# Power.net
KiCad netlist of a schematic drawn in Altium Designer
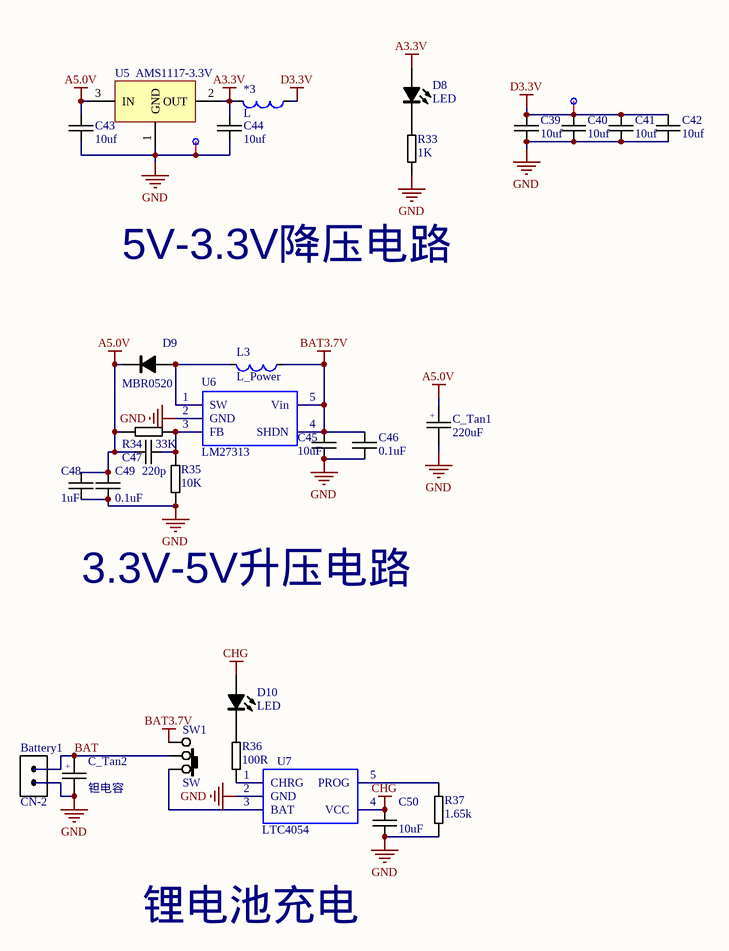
[diagram p0: Power.SchDoc]

(export (version "E")
  (design (tool "Eeschema 10.0.6"))
  (components
    (comp (ref "*3") (value "L") (footprint "0603") (libsource (lib "authuir") (part "L")))
    (comp (ref "*4") (value "Point") (footprint "Point") (libsource (lib "authuir") (part "Point")))
    (comp (ref "*5") (value "Point") (footprint "Point") (libsource (lib "authuir") (part "Point")))
    (comp (ref "Battery1") (value "CN-2") (footprint "SIP-2") (libsource (lib "SIT_开关继电器") (part "CN-2")))
    (comp (ref "C39")
      (value "10uf")
      (footprint "0805-C")
      (description "贴片")
      (libsource (lib "authuir") (part "CAP_Chip"))
    )
    (comp (ref "C40")
      (value "10uf")
      (footprint "0805-C")
      (description "贴片")
      (libsource (lib "authuir") (part "CAP_Chip"))
    )
    (comp (ref "C41")
      (value "10uf")
      (footprint "0805-C")
      (description "贴片")
      (libsource (lib "authuir") (part "CAP_Chip"))
    )
    (comp (ref "C42")
      (value "10uf")
      (footprint "0805-C")
      (description "贴片")
      (libsource (lib "authuir") (part "CAP_Chip"))
    )
    (comp (ref "C43")
      (value "10uf")
      (footprint "0805-C")
      (description "贴片")
      (libsource (lib "authuir") (part "CAP_Chip"))
    )
    (comp (ref "C44")
      (value "10uf")
      (footprint "0805-C")
      (description "贴片")
      (libsource (lib "authuir") (part "CAP_Chip"))
    )
    (comp (ref "C45")
      (value "10uF")
      (footprint "0603")
      (description "贴片")
      (libsource (lib "SIT_电阻电容") (part "CAP_Chip"))
    )
    (comp (ref "C46")
      (value "0.1uF")
      (footprint "0603")
      (description "贴片")
      (libsource (lib "SIT_电阻电容") (part "CAP_Chip"))
    )
    (comp (ref "C47")
      (value "220p")
      (footprint "0603")
      (description "贴片")
      (libsource (lib "SIT_电阻电容") (part "CAP_Chip"))
    )
    (comp (ref "C48")
      (value "1uF")
      (footprint "0603")
      (description "贴片")
      (libsource (lib "SIT_电阻电容") (part "CAP_Chip"))
    )
    (comp (ref "C49")
      (value "0.1uF")
      (footprint "0603")
      (description "贴片")
      (libsource (lib "SIT_电阻电容") (part "CAP_Chip"))
    )
    (comp (ref "C50")
      (value "10uF")
      (footprint "0603")
      (description "贴片")
      (libsource (lib "SIT_电阻电容") (part "CAP_Chip"))
    )
    (comp (ref "C_Tan1") (value "220uF") (footprint "钽电容7343") (libsource (lib "authuir") (part "钽电容")))
    (comp (ref "C_Tan2") (value "钽电容") (footprint "钽电容7343") (libsource (lib "SIT器件") (part "钽电容")))
    (comp (ref "D8")
      (value "LED")
      (footprint "0805-LED")
      (description "贴片")
      (libsource (lib "authuir") (part "LED"))
    )
    (comp (ref "D9")
      (value "MBR0520")
      (footprint "SOD-123-L")
      (description "贴片")
      (libsource (lib "SIT_电阻电容") (part "MBR0520"))
    )
    (comp (ref "D10")
      (value "LED")
      (footprint "0603")
      (description "贴片")
      (libsource (lib "SIT_电阻电容") (part "LED"))
    )
    (comp (ref "L3") (value "L_Power") (footprint "GDSD3316") (libsource (lib "SIT_电阻电容") (part "L_Power")))
    (comp (ref "R33")
      (value "1K")
      (footprint "0805-R")
      (description "贴片")
      (libsource (lib "authuir") (part "RES_Chip"))
    )
    (comp (ref "R34")
      (value "33K")
      (footprint "0603")
      (description "贴片")
      (libsource (lib "SIT_电阻电容") (part "RES_Chip"))
    )
    (comp (ref "R35")
      (value "10K")
      (footprint "0603")
      (description "贴片")
      (libsource (lib "SIT_电阻电容") (part "RES_Chip"))
    )
    (comp (ref "R36")
      (value "100R")
      (footprint "0603")
      (description "贴片")
      (libsource (lib "SIT_电阻电容") (part "RES_Chip"))
    )
    (comp (ref "R37")
      (value "1.65k")
      (footprint "0603")
      (description "贴片")
      (libsource (lib "SIT_电阻电容") (part "RES_Chip"))
    )
    (comp (ref "SW1")
      (value "SW")
      (footprint "SW-SPDT(12.5×6,3)")
      (description "1.09.07.0005")
      (libsource (lib "SIT器件") (part "SW-SPDT(拨动开关,12.5×6×11)"))
    )
    (comp (ref "U5")
      (value "AMS1117-3.3V")
      (footprint "SOT-223")
      (libsource (lib "authuir") (part "AMS1117"))
    )
    (comp (ref "U6") (value "LM27313") (footprint "DBV005_L") (libsource (lib "SIT_模拟芯片") (part "LM27313")))
    (comp (ref "U7") (value "LTC4054") (footprint "DBV005_L") (libsource (lib "SIT_模拟芯片") (part "LTC4054")))
  )
  (nets
    (net (code "1") (name "/BAT") (class "Default")
      (node (ref "Battery1") (pin "1") (pinfunction "1_1") (pintype "passive"))
      (node (ref "C_Tan2") (pin "2") (pinfunction "2_2") (pintype "passive"))
      (node (ref "SW1") (pin "2") (pinfunction "2_2") (pintype "passive"))
    )
    (net (code "2") (name "A3.3V") (class "Default")
      (node (ref "*3") (pin "1") (pinfunction "1_1") (pintype "passive"))
      (node (ref "C44") (pin "1") (pinfunction "1_1") (pintype "passive"))
      (node (ref "D8") (pin "1") (pinfunction "A_1") (pintype "passive"))
      (node (ref "U5") (pin "2") (pinfunction "OUT_2") (pintype "passive"))
    )
    (net (code "3") (name "A5.0V") (class "Default")
      (node (ref "C43") (pin "1") (pinfunction "1_1") (pintype "passive"))
      (node (ref "C47") (pin "1") (pinfunction "1_1") (pintype "passive"))
      (node (ref "C48") (pin "1") (pinfunction "1_1") (pintype "passive"))
      (node (ref "C49") (pin "1") (pinfunction "1_1") (pintype "passive"))
      (node (ref "C_Tan1") (pin "2") (pinfunction "2_2") (pintype "passive"))
      (node (ref "D9") (pin "2") (pinfunction "K_2") (pintype "passive"))
      (node (ref "R34") (pin "1") (pinfunction "1_1") (pintype "passive"))
      (node (ref "U5") (pin "3") (pinfunction "IN_3") (pintype "passive"))
    )
    (net (code "4") (name "BAT3.7V") (class "Default")
      (node (ref "C45") (pin "1") (pinfunction "1_1") (pintype "passive"))
      (node (ref "C46") (pin "1") (pinfunction "1_1") (pintype "passive"))
      (node (ref "L3") (pin "2") (pinfunction "2_2") (pintype "passive"))
      (node (ref "SW1") (pin "3") (pinfunction "3_3") (pintype "passive"))
      (node (ref "U6") (pin "4") (pinfunction "SHDN_4") (pintype "passive"))
      (node (ref "U6") (pin "5") (pinfunction "Vin_5") (pintype "passive"))
    )
    (net (code "5") (name "CHG") (class "Default")
      (node (ref "C50") (pin "1") (pinfunction "1_1") (pintype "passive"))
      (node (ref "D10") (pin "1") (pinfunction "A_1") (pintype "passive"))
      (node (ref "U7") (pin "4") (pinfunction "VCC_4") (pintype "passive"))
    )
    (net (code "6") (name "D3.3V") (class "Default")
      (node (ref "*3") (pin "2") (pinfunction "2_2") (pintype "passive"))
      (node (ref "*4") (pin "1") (pinfunction "Point_1") (pintype "passive"))
      (node (ref "C39") (pin "1") (pinfunction "1_1") (pintype "passive"))
      (node (ref "C40") (pin "1") (pinfunction "1_1") (pintype "passive"))
      (node (ref "C41") (pin "1") (pinfunction "1_1") (pintype "passive"))
      (node (ref "C42") (pin "1") (pinfunction "1_1") (pintype "passive"))
    )
    (net (code "7") (name "GND") (class "Default")
      (node (ref "*5") (pin "1") (pinfunction "Point_1") (pintype "passive"))
      (node (ref "Battery1") (pin "2") (pinfunction "2_2") (pintype "passive"))
      (node (ref "C39") (pin "2") (pinfunction "2_2") (pintype "passive"))
      (node (ref "C40") (pin "2") (pinfunction "2_2") (pintype "passive"))
      (node (ref "C41") (pin "2") (pinfunction "2_2") (pintype "passive"))
      (node (ref "C42") (pin "2") (pinfunction "2_2") (pintype "passive"))
      (node (ref "C43") (pin "2") (pinfunction "2_2") (pintype "passive"))
      (node (ref "C44") (pin "2") (pinfunction "2_2") (pintype "passive"))
      (node (ref "C45") (pin "2") (pinfunction "2_2") (pintype "passive"))
      (node (ref "C46") (pin "2") (pinfunction "2_2") (pintype "passive"))
      (node (ref "C48") (pin "2") (pinfunction "2_2") (pintype "passive"))
      (node (ref "C49") (pin "2") (pinfunction "2_2") (pintype "passive"))
      (node (ref "C50") (pin "2") (pinfunction "2_2") (pintype "passive"))
      (node (ref "C_Tan1") (pin "1") (pinfunction "1_1") (pintype "passive"))
      (node (ref "C_Tan2") (pin "1") (pinfunction "1_1") (pintype "passive"))
      (node (ref "R33") (pin "2") (pinfunction "2_2") (pintype "passive"))
      (node (ref "R35") (pin "2") (pinfunction "2_2") (pintype "passive"))
      (node (ref "R37") (pin "2") (pinfunction "2_2") (pintype "passive"))
      (node (ref "U5") (pin "1") (pinfunction "GND_1") (pintype "passive"))
      (node (ref "U6") (pin "2") (pinfunction "GND_2") (pintype "passive"))
      (node (ref "U7") (pin "2") (pinfunction "GND_2") (pintype "passive"))
    )
    (net (code "8") (name "Net-(D8-K)") (class "Default")
      (node (ref "D8") (pin "2") (pinfunction "K_2") (pintype "passive"))
      (node (ref "R33") (pin "1") (pinfunction "1_1") (pintype "passive"))
    )
    (net (code "9") (name "Net-(D9-A)") (class "Default")
      (node (ref "D9") (pin "1") (pinfunction "A_1") (pintype "passive"))
      (node (ref "L3") (pin "1") (pinfunction "1_1") (pintype "passive"))
      (node (ref "U6") (pin "1") (pinfunction "SW_1") (pintype "passive"))
    )
    (net (code "10") (name "Net-(D10-K)") (class "Default")
      (node (ref "D10") (pin "2") (pinfunction "K_2") (pintype "passive"))
      (node (ref "R36") (pin "1") (pinfunction "1_1") (pintype "passive"))
    )
    (net (code "11") (name "Net-(U6-FB)") (class "Default")
      (node (ref "C47") (pin "2") (pinfunction "2_2") (pintype "passive"))
      (node (ref "R34") (pin "2") (pinfunction "2_2") (pintype "passive"))
      (node (ref "R35") (pin "1") (pinfunction "1_1") (pintype "passive"))
      (node (ref "U6") (pin "3") (pinfunction "FB_3") (pintype "passive"))
    )
    (net (code "12") (name "Net-(U7-BAT)") (class "Default")
      (node (ref "SW1") (pin "1") (pinfunction "1_1") (pintype "passive"))
      (node (ref "U7") (pin "3") (pinfunction "BAT_3") (pintype "passive"))
    )
    (net (code "13") (name "Net-(U7-CHRG)") (class "Default")
      (node (ref "R36") (pin "2") (pinfunction "2_2") (pintype "passive"))
      (node (ref "U7") (pin "1") (pinfunction "CHRG_1") (pintype "passive"))
    )
    (net (code "14") (name "Net-(U7-PROG)") (class "Default")
      (node (ref "R37") (pin "1") (pinfunction "1_1") (pintype "passive"))
      (node (ref "U7") (pin "5") (pinfunction "PROG_5") (pintype "passive"))
    )
  )
)
